# FirstStageAmplifier.net
KiCad netlist of a schematic drawn in Altium Designer
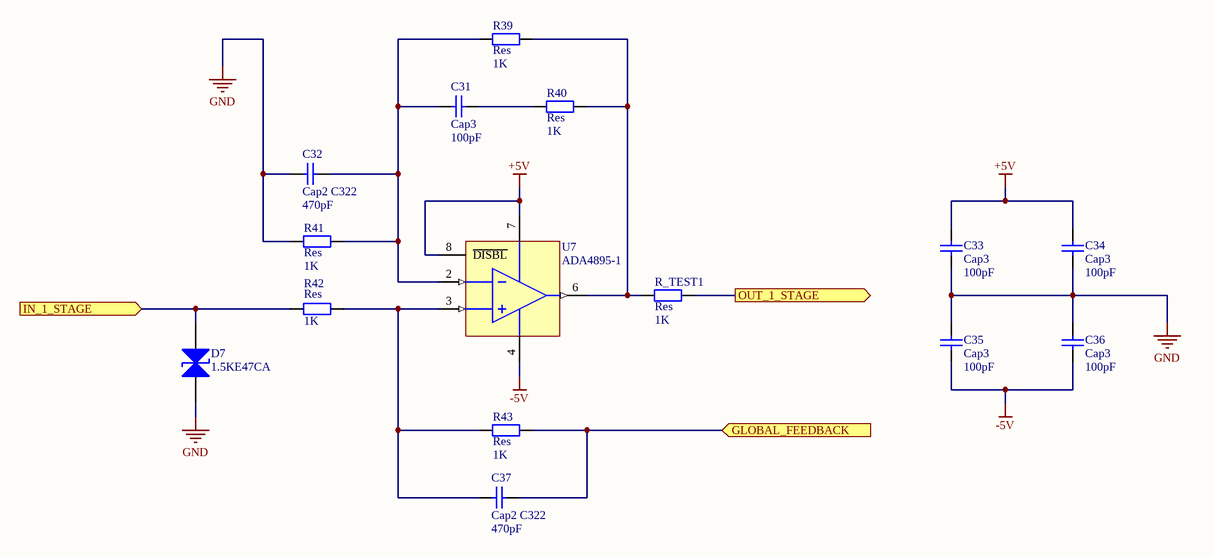
[diagram p0: FirstStageAmplifier.SchDoc]

(export (version "E")
  (design (tool "Eeschema 10.0.6"))
  (components
    (comp (ref "C31")
      (value "Cap3")
      (footprint "CAP_0805_IPC_MD")
      (description "Standard SMD 0805 Capacitor")
      (fields (field (name "ALTIUM_VALUE") "100pF"))
      (libsource (lib "SchematicLib") (part "Cap3"))
    )
    (comp (ref "C32")
      (value "Cap2 C322")
      (footprint "CAP-CERAMIC-200MIL")
      (fields (field (name "ALTIUM_VALUE") "470pF"))
      (libsource (lib "SchematicLib") (part "Cap2"))
    )
    (comp (ref "C33")
      (value "Cap3")
      (footprint "CAP_0805_IPC_MD")
      (description "Standard SMD 0805 Capacitor")
      (fields (field (name "ALTIUM_VALUE") "100pF"))
      (libsource (lib "SchematicLib") (part "Cap3"))
    )
    (comp (ref "C34")
      (value "Cap3")
      (footprint "CAP_0805_IPC_MD")
      (description "Standard SMD 0805 Capacitor")
      (fields (field (name "ALTIUM_VALUE") "100pF"))
      (libsource (lib "SchematicLib") (part "Cap3"))
    )
    (comp (ref "C35")
      (value "Cap3")
      (footprint "CAP_0805_IPC_MD")
      (description "Standard SMD 0805 Capacitor")
      (fields (field (name "ALTIUM_VALUE") "100pF"))
      (libsource (lib "SchematicLib") (part "Cap3"))
    )
    (comp (ref "C36")
      (value "Cap3")
      (footprint "CAP_0805_IPC_MD")
      (description "Standard SMD 0805 Capacitor")
      (fields (field (name "ALTIUM_VALUE") "100pF"))
      (libsource (lib "SchematicLib") (part "Cap3"))
    )
    (comp (ref "C37")
      (value "Cap2 C322")
      (footprint "CAP-CERAMIC-200MIL")
      (fields (field (name "ALTIUM_VALUE") "470pF"))
      (libsource (lib "SchematicLib") (part "Cap2"))
    )
    (comp (ref "D7")
      (value "1.5KE47CA")
      (footprint "DIODE-0.7")
      (description "Transient Voltage Suppressor Diodes; Breakdown V: 44.7...49.4, Stand-off V: 40.2")
      (libsource (lib "SchematicLib") (part "1.5KE47CA"))
    )
    (comp (ref "R39")
      (value "Res")
      (footprint "RESISTOR-10mm")
      (description "Resistor")
      (fields (field (name "ALTIUM_VALUE") "1K"))
      (libsource (lib "SchematicLib") (part "Res"))
    )
    (comp (ref "R40")
      (value "Res")
      (footprint "RESISTOR-10mm")
      (description "Resistor")
      (fields (field (name "ALTIUM_VALUE") "1K"))
      (libsource (lib "SchematicLib") (part "Res"))
    )
    (comp (ref "R41")
      (value "Res")
      (footprint "RESISTOR-10mm")
      (description "Resistor")
      (fields (field (name "ALTIUM_VALUE") "1K"))
      (libsource (lib "SchematicLib") (part "Res"))
    )
    (comp (ref "R42")
      (value "Res")
      (footprint "RESISTOR-10mm")
      (description "Resistor")
      (fields (field (name "ALTIUM_VALUE") "1K"))
      (libsource (lib "") (part "Res_1"))
    )
    (comp (ref "R43")
      (value "Res")
      (footprint "RESISTOR-10mm")
      (description "Resistor")
      (fields (field (name "ALTIUM_VALUE") "1K"))
      (libsource (lib "SchematicLib") (part "Res"))
    )
    (comp (ref "R_TEST1")
      (value "Res")
      (footprint "RESISTOR-10mm")
      (description "Resistor")
      (fields (field (name "ALTIUM_VALUE") "1K"))
      (libsource (lib "") (part "Res_1"))
    )
    (comp (ref "U7")
      (value "ADA4895-1")
      (footprint "SOIC_8_IPC_MD")
      (description "Low Power, 1 nV/√Hz, G ≥ 10 Stable, Rail-to-Rail Output Amplifier")
      (libsource (lib "SchematicLib") (part "ADA4895-1"))
    )
  )
  (nets
    (net (code "1") (name "+5V") (class "Default")
      (node (ref "C33") (pin "2") (pinfunction "2_2") (pintype "passive"))
      (node (ref "C34") (pin "2") (pinfunction "2_2") (pintype "passive"))
      (node (ref "U7") (pin "7") (pinfunction "VDD_7") (pintype "power_in"))
      (node (ref "U7") (pin "8") (pinfunction "~{DISBL}_8") (pintype "passive"))
    )
    (net (code "2") (name "-5V") (class "Default")
      (node (ref "C35") (pin "1") (pinfunction "1_1") (pintype "passive"))
      (node (ref "C36") (pin "1") (pinfunction "1_1") (pintype "passive"))
      (node (ref "U7") (pin "4") (pinfunction "VSS_4") (pintype "power_in"))
    )
    (net (code "3") (name "/GLOBAL_FEEDBACK") (class "Default")
      (node (ref "C37") (pin "2") (pinfunction "2_2") (pintype "passive"))
      (node (ref "R43") (pin "2") (pinfunction "2_2") (pintype "passive"))
    )
    (net (code "4") (name "/IN_1_STAGE") (class "Default")
      (node (ref "D7") (pin "2") (pinfunction "IN2_2") (pintype "passive"))
      (node (ref "R42") (pin "1") (pinfunction "1_1") (pintype "passive"))
    )
    (net (code "5") (name "/OUT_1_STAGE") (class "Default")
      (node (ref "R_TEST1") (pin "2") (pinfunction "2_2") (pintype "passive"))
    )
    (net (code "6") (name "GND") (class "Default")
      (node (ref "C32") (pin "1") (pinfunction "1_1") (pintype "passive"))
      (node (ref "C33") (pin "1") (pinfunction "1_1") (pintype "passive"))
      (node (ref "C34") (pin "1") (pinfunction "1_1") (pintype "passive"))
      (node (ref "C35") (pin "2") (pinfunction "2_2") (pintype "passive"))
      (node (ref "C36") (pin "2") (pinfunction "2_2") (pintype "passive"))
      (node (ref "D7") (pin "1") (pinfunction "IN1_1") (pintype "passive"))
      (node (ref "R41") (pin "1") (pinfunction "1_1") (pintype "passive"))
    )
    (net (code "7") (name "Net-(C31-Pad2)") (class "Default")
      (node (ref "C31") (pin "2") (pinfunction "2_2") (pintype "passive"))
      (node (ref "R40") (pin "1") (pinfunction "1_1") (pintype "passive"))
    )
    (net (code "8") (name "Net-(U7-VIND+)") (class "Default")
      (node (ref "C37") (pin "1") (pinfunction "1_1") (pintype "passive"))
      (node (ref "R42") (pin "2") (pinfunction "2_2") (pintype "passive"))
      (node (ref "R43") (pin "1") (pinfunction "1_1") (pintype "passive"))
      (node (ref "U7") (pin "3") (pinfunction "VIND+_3") (pintype "input"))
    )
    (net (code "9") (name "Net-(U7-VIND-)") (class "Default")
      (node (ref "C31") (pin "1") (pinfunction "1_1") (pintype "passive"))
      (node (ref "C32") (pin "2") (pinfunction "2_2") (pintype "passive"))
      (node (ref "R39") (pin "1") (pinfunction "1_1") (pintype "passive"))
      (node (ref "R41") (pin "2") (pinfunction "2_2") (pintype "passive"))
      (node (ref "U7") (pin "2") (pinfunction "VIND-_2") (pintype "input"))
    )
    (net (code "10") (name "Net-(U7-VOUTD)") (class "Default")
      (node (ref "R39") (pin "2") (pinfunction "2_2") (pintype "passive"))
      (node (ref "R40") (pin "2") (pinfunction "2_2") (pintype "passive"))
      (node (ref "R_TEST1") (pin "1") (pinfunction "1_1") (pintype "passive"))
      (node (ref "U7") (pin "6") (pinfunction "VOUTD_6") (pintype "output"))
    )
  )
)
